# spring_2020_swarm.net
KiCad netlist of a schematic drawn in EAGLE
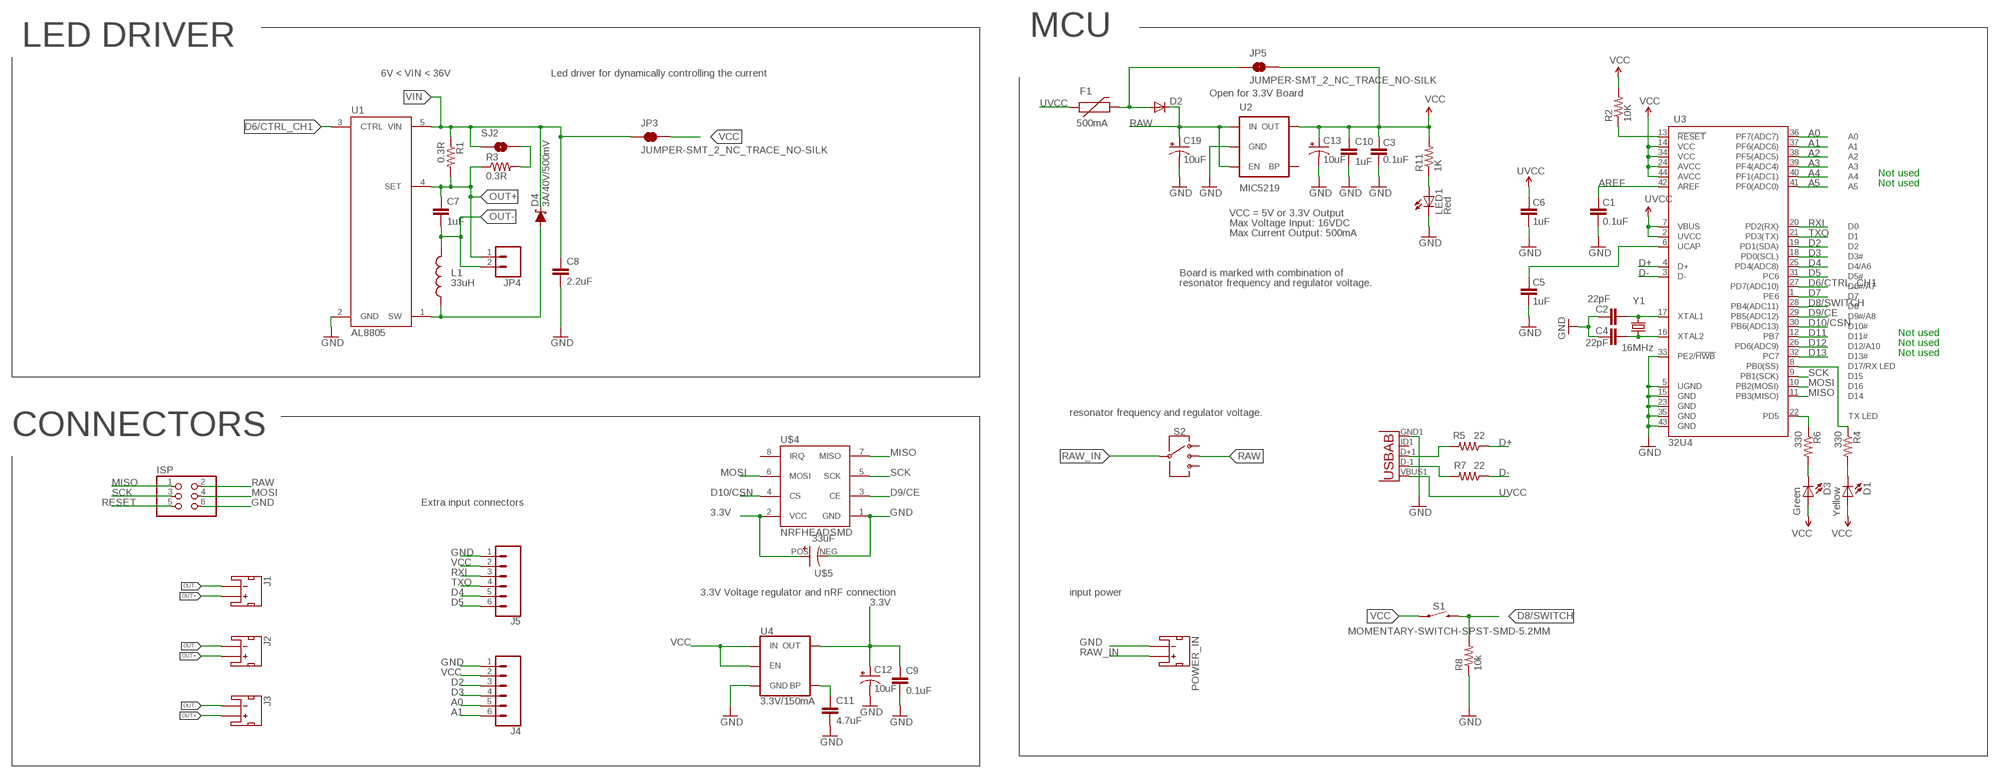
[diagram p0: schematic, sheet 1]

(export (version "E")
  (design (tool "Eeschema 10.0.6"))
  (components
    (comp (ref "C1")
      (value "0.1uF")
      (footprint "eagle-import:0603-CAP")
      (libsource (lib "eagle-import") (part "CAP0603-CAP"))
    )
    (comp (ref "C2")
      (value "22pF")
      (footprint "eagle-import:0603-CAP")
      (libsource (lib "eagle-import") (part "CAP0603-CAP"))
    )
    (comp (ref "C3")
      (value "0.1uF")
      (footprint "eagle-import:0603-CAP")
      (libsource (lib "eagle-import") (part "CAP0603-CAP"))
    )
    (comp (ref "C4")
      (value "22pF")
      (footprint "eagle-import:0603-CAP")
      (libsource (lib "eagle-import") (part "CAP0603-CAP"))
    )
    (comp (ref "C5")
      (value "1uF")
      (footprint "eagle-import:0603-CAP")
      (libsource (lib "eagle-import") (part "CAP0603-CAP"))
    )
    (comp (ref "C6")
      (value "1uF")
      (footprint "eagle-import:0603-CAP")
      (libsource (lib "eagle-import") (part "CAP0603-CAP"))
    )
    (comp (ref "C7")
      (value "1uF")
      (footprint "eagle-import:1206-CAP")
      (libsource (lib "eagle-import") (part "1.0UF50V10%(1206)"))
    )
    (comp (ref "C8")
      (value "2.2uF")
      (footprint "eagle-import:1206-CAP")
      (libsource (lib "eagle-import") (part "2.2UF50V10%(1206)"))
    )
    (comp (ref "C9")
      (value "0.1uF")
      (footprint "eagle-import:0603")
      (libsource (lib "eagle-import") (part "0.1UF-0603-25V-5%"))
    )
    (comp (ref "C10")
      (value "1uF")
      (footprint "eagle-import:0603-CAP")
      (libsource (lib "eagle-import") (part "CAP0603-CAP"))
    )
    (comp (ref "C11")
      (value "4.7uF")
      (footprint "eagle-import:0603")
      (libsource (lib "eagle-import") (part "4.7UF0603"))
    )
    (comp (ref "C12")
      (value "10uF")
      (footprint "eagle-import:EIA3216")
      (libsource (lib "eagle-import") (part "CAP_POL1206"))
    )
    (comp (ref "C13")
      (value "10uF")
      (footprint "eagle-import:EIA3216")
      (libsource (lib "eagle-import") (part "CAP_POL1206"))
    )
    (comp (ref "C19")
      (value "10uF")
      (footprint "eagle-import:EIA3216")
      (libsource (lib "eagle-import") (part "CAP_POL1206"))
    )
    (comp (ref "D1")
      (value "Yellow")
      (footprint "eagle-import:LED-0603")
      (libsource (lib "eagle-import") (part "LED0603"))
    )
    (comp (ref "D2")
      (value "DIODESOD")
      (footprint "eagle-import:SOD-323")
      (libsource (lib "eagle-import") (part "DIODESOD"))
    )
    (comp (ref "D3")
      (value "Green")
      (footprint "eagle-import:LED-0603")
      (libsource (lib "eagle-import") (part "LED0603"))
    )
    (comp (ref "D4")
      (value "3A/40V/500mV")
      (footprint "eagle-import:SMA-DIODE")
      (libsource (lib "eagle-import") (part "DIODE-SCHOTTKY-B340A"))
    )
    (comp (ref "F1")
      (value "500mA")
      (footprint "eagle-import:PTC-1206")
      (libsource (lib "eagle-import") (part "PTCSMD"))
    )
    (comp (ref "ISP")
      (value "PINHD-2X3-SMD")
      (footprint "eagle-import:2X03SMD")
      (libsource (lib "eagle-import") (part "PINHD-2X3-SMD"))
    )
    (comp (ref "J1")
      (value "JST_2MM_MALE")
      (footprint "eagle-import:JST-2-SMD")
      (libsource (lib "eagle-import") (part "JST_2MM_MALE"))
    )
    (comp (ref "J2")
      (value "JST_2MM_MALE")
      (footprint "eagle-import:JST-2-SMD")
      (libsource (lib "eagle-import") (part "JST_2MM_MALE"))
    )
    (comp (ref "J3")
      (value "JST_2MM_MALE")
      (footprint "eagle-import:JST-2-SMD")
      (libsource (lib "eagle-import") (part "JST_2MM_MALE"))
    )
    (comp (ref "J4")
      (value "CONN_06SMD-1MM")
      (footprint "eagle-import:1X06-1MM")
      (libsource (lib "eagle-import") (part "CONN_06SMD-1MM"))
    )
    (comp (ref "J5")
      (value "CONN_06SMD-1MM")
      (footprint "eagle-import:1X06-1MM")
      (libsource (lib "eagle-import") (part "CONN_06SMD-1MM"))
    )
    (comp (ref "JP3")
      (value "JUMPER-SMT_2_NC_TRACE_NO-SILK")
      (footprint "eagle-import:SMT-JUMPER_2_NC_TRACE_NO-SILK")
      (libsource (lib "eagle-import") (part "JUMPER-SMT_2_NC_TRACE_NO-SILK"))
    )
    (comp (ref "JP4")
      (value "CONN_02")
      (footprint "eagle-import:1X02")
      (libsource (lib "eagle-import") (part "CONN_02"))
    )
    (comp (ref "JP5")
      (value "JUMPER-SMT_2_NC_TRACE_NO-SILK")
      (footprint "eagle-import:SMT-JUMPER_2_NC_TRACE_NO-SILK")
      (libsource (lib "eagle-import") (part "JUMPER-SMT_2_NC_TRACE_NO-SILK"))
    )
    (comp (ref "L1")
      (value "33uH")
      (footprint "eagle-import:SRN6045")
      (libsource (lib "eagle-import") (part "INDUCTORBOURNS_SRN6045"))
    )
    (comp (ref "LED1")
      (value "Red")
      (footprint "eagle-import:LED-0603")
      (libsource (lib "eagle-import") (part "LED0603"))
    )
    (comp (ref "POWER_IN")
      (value "JST_2MM_MALE")
      (footprint "eagle-import:JST-2-SMD")
      (libsource (lib "eagle-import") (part "JST_2MM_MALE"))
    )
    (comp (ref "R1")
      (value "0.3R")
      (footprint "eagle-import:0805")
      (libsource (lib "eagle-import") (part "0.3OHM-1/8W-1%(0805)"))
    )
    (comp (ref "R2")
      (value "10K")
      (footprint "eagle-import:0603-RES")
      (libsource (lib "eagle-import") (part "RESISTOR0603-RES"))
    )
    (comp (ref "R3")
      (value "0.3R")
      (footprint "eagle-import:0805")
      (libsource (lib "eagle-import") (part "0.3OHM-1/8W-1%(0805)"))
    )
    (comp (ref "R4")
      (value "330")
      (footprint "eagle-import:0603-RES")
      (libsource (lib "eagle-import") (part "RESISTOR0603-RES"))
    )
    (comp (ref "R5")
      (value "22")
      (footprint "eagle-import:0603-RES")
      (libsource (lib "eagle-import") (part "RESISTOR0603-RES"))
    )
    (comp (ref "R6")
      (value "330")
      (footprint "eagle-import:0603-RES")
      (libsource (lib "eagle-import") (part "RESISTOR0603-RES"))
    )
    (comp (ref "R7")
      (value "22")
      (footprint "eagle-import:0603-RES")
      (libsource (lib "eagle-import") (part "RESISTOR0603-RES"))
    )
    (comp (ref "R8")
      (value "10k")
      (footprint "eagle-import:0603-RES")
      (libsource (lib "eagle-import") (part "RESISTOR0603-RES"))
    )
    (comp (ref "R11")
      (value "1K")
      (footprint "eagle-import:0603-RES")
      (libsource (lib "eagle-import") (part "RESISTOR0603-RES"))
    )
    (comp (ref "S1")
      (value "MOMENTARY-SWITCH-SPST-SMD-5.2MM")
      (footprint "eagle-import:TACTILE_SWITCH_SMD_5.2MM")
      (libsource (lib "eagle-import") (part "MOMENTARY-SWITCH-SPST-SMD-5.2MM"))
    )
    (comp (ref "S2")
      (value "SWITCH-SP3T-SMD")
      (footprint "eagle-import:SWITCH_SP3T_SMD")
      (libsource (lib "eagle-import") (part "SWITCH-SP3T-SMD"))
    )
    (comp (ref "SJ2")
      (value "NO Jumper")
      (footprint "eagle-import:PAD-JUMPER-2-NO_NO_SILK")
      (libsource (lib "eagle-import") (part "JUMPER-PAD-2-NO"))
    )
    (comp (ref "U$4")
      (value "NRFHEADSMD")
      (footprint "eagle-import:2.54MM")
      (libsource (lib "eagle-import") (part "NRFHEADSMD"))
    )
    (comp (ref "U$5")
      (value "33uF")
      (footprint "eagle-import:PANASONIC-CAP-SMD-C")
      (libsource (lib "eagle-import") (part "POLCAP-PANASONIC-SMD-C"))
    )
    (comp (ref "U1")
      (value "AL8805")
      (footprint "eagle-import:SOT23-5")
      (libsource (lib "eagle-import") (part "AL8805"))
    )
    (comp (ref "U2")
      (value "MIC5219")
      (footprint "eagle-import:SOT23-5")
      (libsource (lib "eagle-import") (part "V_REG_LDOSMD"))
    )
    (comp (ref "U3")
      (value "32U4")
      (footprint "eagle-import:TQFP44")
      (libsource (lib "eagle-import") (part "ATMEGA32U4TQFP-44"))
    )
    (comp (ref "U4")
      (value "3.3V/150mA")
      (footprint "eagle-import:SOT23-5")
      (libsource (lib "eagle-import") (part "V_REG_MIC52053.3V"))
    )
    (comp (ref "X1")
      (value "USB-ABIN&OUT")
      (footprint "eagle-import:USB-AB-MICRO-SMD-V03-IN&OUT")
      (libsource (lib "eagle-import") (part "USB-ABIN&OUT"))
    )
    (comp (ref "Y1")
      (value "16MHz")
      (footprint "eagle-import:CRYSTAL-SMD-5X3")
      (libsource (lib "eagle-import") (part "CRYSTAL5X3"))
    )
  )
  (nets
    (net (code "1") (name "/3.3V") (class "Default")
      (node (ref "C12") (pin "A") (pinfunction "+_A") (pintype "passive"))
      (node (ref "C9") (pin "1") (pinfunction "1_1") (pintype "passive"))
      (node (ref "U$4") (pin "2") (pinfunction "VCC_2") (pintype "bidirectional"))
      (node (ref "U$5") (pin "POS") (pinfunction "+_POS") (pintype "bidirectional"))
      (node (ref "U4") (pin "5") (pinfunction "OUT_5") (pintype "passive"))
    )
    (net (code "2") (name "/A0") (class "Default")
      (node (ref "J4") (pin "5") (pinfunction "5_5") (pintype "passive"))
      (node (ref "U3") (pin "36") (pinfunction "PF7(ADC7)_36") (pintype "bidirectional"))
    )
    (net (code "3") (name "/A1") (class "Default")
      (node (ref "J4") (pin "6") (pinfunction "6_6") (pintype "passive"))
      (node (ref "U3") (pin "37") (pinfunction "PF6(ADC6)_37") (pintype "bidirectional"))
    )
    (net (code "4") (name "/A2") (class "Default")
      (node (ref "U3") (pin "38") (pinfunction "PF5(ADC5)_38") (pintype "bidirectional"))
    )
    (net (code "5") (name "/A3") (class "Default")
      (node (ref "U3") (pin "39") (pinfunction "PF4(ADC4)_39") (pintype "bidirectional"))
    )
    (net (code "6") (name "/A4") (class "Default")
      (node (ref "U3") (pin "40") (pinfunction "PF1(ADC1)_40") (pintype "bidirectional"))
    )
    (net (code "7") (name "/A5") (class "Default")
      (node (ref "U3") (pin "41") (pinfunction "PF0(ADC0)_41") (pintype "bidirectional"))
    )
    (net (code "8") (name "/AREF") (class "Default")
      (node (ref "C1") (pin "2") (pinfunction "2_2") (pintype "passive"))
      (node (ref "U3") (pin "42") (pinfunction "AREF_42") (pintype "bidirectional"))
    )
    (net (code "9") (name "/D+") (class "Default")
      (node (ref "R5") (pin "1") (pinfunction "1_1") (pintype "passive"))
      (node (ref "U3") (pin "4") (pinfunction "D+_4") (pintype "bidirectional"))
    )
    (net (code "10") (name "/D-") (class "Default")
      (node (ref "R7") (pin "1") (pinfunction "1_1") (pintype "passive"))
      (node (ref "U3") (pin "3") (pinfunction "D-_3") (pintype "bidirectional"))
    )
    (net (code "11") (name "/D2") (class "Default")
      (node (ref "J4") (pin "3") (pinfunction "3_3") (pintype "passive"))
      (node (ref "U3") (pin "19") (pinfunction "PD1(SDA)_19") (pintype "bidirectional"))
    )
    (net (code "12") (name "/D3") (class "Default")
      (node (ref "J4") (pin "4") (pinfunction "4_4") (pintype "passive"))
      (node (ref "U3") (pin "18") (pinfunction "PD0(SCL)_18") (pintype "bidirectional"))
    )
    (net (code "13") (name "/D4") (class "Default")
      (node (ref "J5") (pin "5") (pinfunction "5_5") (pintype "passive"))
      (node (ref "U3") (pin "25") (pinfunction "PD4(ADC8)_25") (pintype "bidirectional"))
    )
    (net (code "14") (name "/D5") (class "Default")
      (node (ref "J5") (pin "6") (pinfunction "6_6") (pintype "passive"))
      (node (ref "U3") (pin "31") (pinfunction "PC6_31") (pintype "bidirectional"))
    )
    (net (code "15") (name "/D7") (class "Default")
      (node (ref "U3") (pin "1") (pinfunction "PE6_1") (pintype "bidirectional"))
    )
    (net (code "16") (name "/D9{slash}CE") (class "Default")
      (node (ref "U$4") (pin "3") (pinfunction "CE_3") (pintype "bidirectional"))
      (node (ref "U3") (pin "29") (pinfunction "PB5(ADC12)_29") (pintype "bidirectional"))
    )
    (net (code "17") (name "/D10{slash}CSN") (class "Default")
      (node (ref "U$4") (pin "4") (pinfunction "CS_4") (pintype "bidirectional"))
      (node (ref "U3") (pin "30") (pinfunction "PB6(ADC13)_30") (pintype "bidirectional"))
    )
    (net (code "18") (name "/D11") (class "Default")
      (node (ref "U3") (pin "12") (pinfunction "PB7_12") (pintype "bidirectional"))
    )
    (net (code "19") (name "/D12") (class "Default")
      (node (ref "U3") (pin "26") (pinfunction "PD6(ADC9)_26") (pintype "bidirectional"))
    )
    (net (code "20") (name "/D13") (class "Default")
      (node (ref "U3") (pin "32") (pinfunction "PC7_32") (pintype "bidirectional"))
    )
    (net (code "21") (name "/MISO") (class "Default")
      (node (ref "ISP") (pin "1") (pinfunction "1_1") (pintype "passive"))
      (node (ref "U$4") (pin "7") (pinfunction "MISO_7") (pintype "bidirectional"))
      (node (ref "U3") (pin "11") (pinfunction "PB3(MISO)_11") (pintype "bidirectional"))
    )
    (net (code "22") (name "/MOSI") (class "Default")
      (node (ref "ISP") (pin "4") (pinfunction "4_4") (pintype "passive"))
      (node (ref "U$4") (pin "6") (pinfunction "MOSI_6") (pintype "bidirectional"))
      (node (ref "U3") (pin "10") (pinfunction "PB2(MOSI)_10") (pintype "bidirectional"))
    )
    (net (code "23") (name "/RESET") (class "Default")
      (node (ref "ISP") (pin "5") (pinfunction "5_5") (pintype "passive"))
      (node (ref "R2") (pin "1") (pinfunction "1_1") (pintype "passive"))
      (node (ref "U3") (pin "13") (pinfunction "~{RESET}_13") (pintype "bidirectional"))
    )
    (net (code "24") (name "/RXI") (class "Default")
      (node (ref "J5") (pin "3") (pinfunction "3_3") (pintype "passive"))
      (node (ref "U3") (pin "20") (pinfunction "PD2(RX)_20") (pintype "bidirectional"))
    )
    (net (code "25") (name "/SCK") (class "Default")
      (node (ref "ISP") (pin "3") (pinfunction "3_3") (pintype "passive"))
      (node (ref "U$4") (pin "5") (pinfunction "SCK_5") (pintype "bidirectional"))
      (node (ref "U3") (pin "9") (pinfunction "PB1(SCK)_9") (pintype "bidirectional"))
    )
    (net (code "26") (name "/TXO") (class "Default")
      (node (ref "J5") (pin "4") (pinfunction "4_4") (pintype "passive"))
      (node (ref "U3") (pin "21") (pinfunction "PD3(TX)_21") (pintype "bidirectional"))
    )
    (net (code "27") (name "D6{slash}CTRL_CH1") (class "Default")
      (node (ref "U1") (pin "3") (pinfunction "CTRL_3") (pintype "bidirectional"))
      (node (ref "U3") (pin "27") (pinfunction "PD7(ADC10)_27") (pintype "bidirectional"))
    )
    (net (code "28") (name "D8{slash}SWITCH") (class "Default")
      (node (ref "R8") (pin "2") (pinfunction "2_2") (pintype "passive"))
      (node (ref "S1") (pin "3") (pinfunction "2_3") (pintype "passive"))
      (node (ref "U3") (pin "28") (pinfunction "PB4(ADC11)_28") (pintype "bidirectional"))
    )
    (net (code "29") (name "GND") (class "Default")
      (node (ref "C1") (pin "1") (pinfunction "1_1") (pintype "passive"))
      (node (ref "C10") (pin "2") (pinfunction "2_2") (pintype "passive"))
      (node (ref "C11") (pin "2") (pinfunction "2_2") (pintype "passive"))
      (node (ref "C12") (pin "C") (pinfunction "-_C") (pintype "passive"))
      (node (ref "C13") (pin "C") (pinfunction "-_C") (pintype "passive"))
      (node (ref "C19") (pin "C") (pinfunction "-_C") (pintype "passive"))
      (node (ref "C2") (pin "2") (pinfunction "2_2") (pintype "passive"))
      (node (ref "C3") (pin "1") (pinfunction "1_1") (pintype "passive"))
      (node (ref "C4") (pin "2") (pinfunction "2_2") (pintype "passive"))
      (node (ref "C5") (pin "1") (pinfunction "1_1") (pintype "passive"))
      (node (ref "C6") (pin "1") (pinfunction "1_1") (pintype "passive"))
      (node (ref "C8") (pin "2") (pinfunction "2_2") (pintype "passive"))
      (node (ref "C9") (pin "2") (pinfunction "2_2") (pintype "passive"))
      (node (ref "ISP") (pin "6") (pinfunction "6_6") (pintype "passive"))
      (node (ref "J4") (pin "1") (pinfunction "1_1") (pintype "passive"))
      (node (ref "J5") (pin "1") (pinfunction "1_1") (pintype "passive"))
      (node (ref "LED1") (pin "C") (pinfunction "C_C") (pintype "passive"))
      (node (ref "POWER_IN") (pin "1") (pinfunction "-_1") (pintype "bidirectional"))
      (node (ref "R8") (pin "1") (pinfunction "1_1") (pintype "passive"))
      (node (ref "U$4") (pin "1") (pinfunction "GND_1") (pintype "bidirectional"))
      (node (ref "U$5") (pin "NEG") (pinfunction "-_NEG") (pintype "bidirectional"))
      (node (ref "U1") (pin "2") (pinfunction "GND_2") (pintype "bidirectional"))
      (node (ref "U2") (pin "2") (pinfunction "GND_2") (pintype "input"))
      (node (ref "U3") (pin "15") (pinfunction "GND_15") (pintype "bidirectional"))
      (node (ref "U3") (pin "23") (pinfunction "GND_23") (pintype "bidirectional"))
      (node (ref "U3") (pin "33") (pinfunction "PE2/~{HWB}_33") (pintype "bidirectional"))
      (node (ref "U3") (pin "35") (pinfunction "GND_35") (pintype "bidirectional"))
      (node (ref "U3") (pin "43") (pinfunction "GND_43") (pintype "bidirectional"))
      (node (ref "U3") (pin "5") (pinfunction "UGND_5") (pintype "bidirectional"))
      (node (ref "U4") (pin "2") (pinfunction "GND_2") (pintype "input"))
      (node (ref "X1") (pin "GND1") (pinfunction "GND_GND1") (pintype "bidirectional"))
    )
    (net (code "30") (name "Net-(D1-PadC)") (class "Default")
      (node (ref "D1") (pin "C") (pinfunction "C_C") (pintype "passive"))
      (node (ref "R4") (pin "2") (pinfunction "2_2") (pintype "passive"))
    )
    (net (code "31") (name "Net-(D2-A)") (class "Default")
      (node (ref "D2") (pin "2") (pinfunction "A_2") (pintype "passive"))
      (node (ref "F1") (pin "2") (pinfunction "2_2") (pintype "bidirectional"))
      (node (ref "JP5") (pin "1") (pinfunction "1_1") (pintype "passive"))
    )
    (net (code "32") (name "Net-(D3-PadC)") (class "Default")
      (node (ref "D3") (pin "C") (pinfunction "C_C") (pintype "passive"))
      (node (ref "R6") (pin "2") (pinfunction "2_2") (pintype "passive"))
    )
    (net (code "33") (name "Net-(LED1-PadA)") (class "Default")
      (node (ref "LED1") (pin "A") (pinfunction "A_A") (pintype "passive"))
      (node (ref "R11") (pin "1") (pinfunction "1_1") (pintype "passive"))
    )
    (net (code "34") (name "Net-(R3-Pad2)") (class "Default")
      (node (ref "R3") (pin "2") (pinfunction "2_2") (pintype "passive"))
      (node (ref "SJ2") (pin "2") (pinfunction "2_2") (pintype "passive"))
    )
    (net (code "35") (name "Net-(U1-SW)") (class "Default")
      (node (ref "D4") (pin "A") (pinfunction "A_A") (pintype "passive"))
      (node (ref "L1") (pin "1") (pinfunction "1_1") (pintype "passive"))
      (node (ref "U1") (pin "1") (pinfunction "SW_1") (pintype "bidirectional"))
    )
    (net (code "36") (name "Net-(U3-PB0(SS))") (class "Default")
      (node (ref "R4") (pin "1") (pinfunction "1_1") (pintype "passive"))
      (node (ref "U3") (pin "8") (pinfunction "PB0(SS)_8") (pintype "bidirectional"))
    )
    (net (code "37") (name "Net-(U3-PD5)") (class "Default")
      (node (ref "R6") (pin "1") (pinfunction "1_1") (pintype "passive"))
      (node (ref "U3") (pin "22") (pinfunction "PD5_22") (pintype "bidirectional"))
    )
    (net (code "38") (name "Net-(U3-UCAP)") (class "Default")
      (node (ref "C5") (pin "2") (pinfunction "2_2") (pintype "passive"))
      (node (ref "U3") (pin "6") (pinfunction "UCAP_6") (pintype "bidirectional"))
    )
    (net (code "39") (name "Net-(U3-XTAL1)") (class "Default")
      (node (ref "C2") (pin "1") (pinfunction "1_1") (pintype "passive"))
      (node (ref "U3") (pin "17") (pinfunction "XTAL1_17") (pintype "bidirectional"))
      (node (ref "Y1") (pin "3") (pinfunction "2_3") (pintype "passive"))
    )
    (net (code "40") (name "Net-(U3-XTAL2)") (class "Default")
      (node (ref "C4") (pin "1") (pinfunction "1_1") (pintype "passive"))
      (node (ref "U3") (pin "16") (pinfunction "XTAL2_16") (pintype "bidirectional"))
      (node (ref "Y1") (pin "1") (pinfunction "1_1") (pintype "passive"))
    )
    (net (code "41") (name "Net-(U4-BP)") (class "Default")
      (node (ref "C11") (pin "1") (pinfunction "1_1") (pintype "passive"))
      (node (ref "U4") (pin "4") (pinfunction "BP_4") (pintype "input"))
    )
    (net (code "42") (name "Net-(X1-D+)") (class "Default")
      (node (ref "R5") (pin "2") (pinfunction "2_2") (pintype "passive"))
      (node (ref "X1") (pin "D+1") (pinfunction "D+_D+1") (pintype "bidirectional"))
    )
    (net (code "43") (name "Net-(X1-D-)") (class "Default")
      (node (ref "R7") (pin "2") (pinfunction "2_2") (pintype "passive"))
      (node (ref "X1") (pin "D-1") (pinfunction "D-_D-1") (pintype "bidirectional"))
    )
    (net (code "44") (name "OUT+") (class "Default")
      (node (ref "C7") (pin "1") (pinfunction "1_1") (pintype "passive"))
      (node (ref "J1") (pin "2") (pinfunction "+_2") (pintype "bidirectional"))
      (node (ref "J2") (pin "2") (pinfunction "+_2") (pintype "bidirectional"))
      (node (ref "J3") (pin "2") (pinfunction "+_2") (pintype "bidirectional"))
      (node (ref "JP4") (pin "1") (pinfunction "1_1") (pintype "passive"))
      (node (ref "R1") (pin "2") (pinfunction "2_2") (pintype "passive"))
      (node (ref "R3") (pin "1") (pinfunction "1_1") (pintype "passive"))
      (node (ref "U1") (pin "4") (pinfunction "SET_4") (pintype "bidirectional"))
    )
    (net (code "45") (name "OUT-") (class "Default")
      (node (ref "C7") (pin "2") (pinfunction "2_2") (pintype "passive"))
      (node (ref "J1") (pin "1") (pinfunction "-_1") (pintype "bidirectional"))
      (node (ref "J2") (pin "1") (pinfunction "-_1") (pintype "bidirectional"))
      (node (ref "J3") (pin "1") (pinfunction "-_1") (pintype "bidirectional"))
      (node (ref "JP4") (pin "2") (pinfunction "2_2") (pintype "passive"))
      (node (ref "L1") (pin "2") (pinfunction "2_2") (pintype "passive"))
    )
    (net (code "46") (name "RAW") (class "Default")
      (node (ref "C19") (pin "A") (pinfunction "+_A") (pintype "passive"))
      (node (ref "D2") (pin "1") (pinfunction "C_1") (pintype "passive"))
      (node (ref "ISP") (pin "2") (pinfunction "2_2") (pintype "passive"))
      (node (ref "S2") (pin "2") (pinfunction "2_2") (pintype "bidirectional"))
      (node (ref "U2") (pin "1") (pinfunction "IN_1") (pintype "input"))
      (node (ref "U2") (pin "3") (pinfunction "EN_3") (pintype "input"))
    )
    (net (code "47") (name "RAW_IN") (class "Default")
      (node (ref "POWER_IN") (pin "2") (pinfunction "+_2") (pintype "bidirectional"))
      (node (ref "S2") (pin "3") (pinfunction "3_3") (pintype "bidirectional"))
    )
    (net (code "48") (name "UVCC") (class "Default")
      (node (ref "C6") (pin "2") (pinfunction "2_2") (pintype "passive"))
      (node (ref "F1") (pin "1") (pinfunction "1_1") (pintype "bidirectional"))
      (node (ref "U3") (pin "2") (pinfunction "UVCC_2") (pintype "bidirectional"))
      (node (ref "U3") (pin "7") (pinfunction "VBUS_7") (pintype "bidirectional"))
      (node (ref "X1") (pin "VBUS1") (pinfunction "VBUS_VBUS1") (pintype "bidirectional"))
    )
    (net (code "49") (name "VCC") (class "Default")
      (node (ref "C10") (pin "1") (pinfunction "1_1") (pintype "passive"))
      (node (ref "C13") (pin "A") (pinfunction "+_A") (pintype "passive"))
      (node (ref "C3") (pin "2") (pinfunction "2_2") (pintype "passive"))
      (node (ref "D1") (pin "A") (pinfunction "A_A") (pintype "passive"))
      (node (ref "D3") (pin "A") (pinfunction "A_A") (pintype "passive"))
      (node (ref "J4") (pin "2") (pinfunction "2_2") (pintype "passive"))
      (node (ref "J5") (pin "2") (pinfunction "2_2") (pintype "passive"))
      (node (ref "JP3") (pin "2") (pinfunction "2_2") (pintype "passive"))
      (node (ref "JP5") (pin "2") (pinfunction "2_2") (pintype "passive"))
      (node (ref "R11") (pin "2") (pinfunction "2_2") (pintype "passive"))
      (node (ref "R2") (pin "2") (pinfunction "2_2") (pintype "passive"))
      (node (ref "S1") (pin "1") (pinfunction "1_1") (pintype "passive"))
      (node (ref "U2") (pin "5") (pinfunction "OUT_5") (pintype "passive"))
      (node (ref "U3") (pin "14") (pinfunction "VCC_14") (pintype "bidirectional"))
      (node (ref "U3") (pin "24") (pinfunction "AVCC_24") (pintype "bidirectional"))
      (node (ref "U3") (pin "34") (pinfunction "VCC_34") (pintype "bidirectional"))
      (node (ref "U3") (pin "44") (pinfunction "AVCC_44") (pintype "bidirectional"))
      (node (ref "U4") (pin "1") (pinfunction "IN_1") (pintype "input"))
      (node (ref "U4") (pin "3") (pinfunction "EN_3") (pintype "input"))
    )
    (net (code "50") (name "VIN") (class "Default")
      (node (ref "C8") (pin "1") (pinfunction "1_1") (pintype "passive"))
      (node (ref "D4") (pin "C") (pinfunction "C_C") (pintype "passive"))
      (node (ref "JP3") (pin "1") (pinfunction "1_1") (pintype "passive"))
      (node (ref "R1") (pin "1") (pinfunction "1_1") (pintype "passive"))
      (node (ref "SJ2") (pin "1") (pinfunction "1_1") (pintype "passive"))
      (node (ref "U1") (pin "5") (pinfunction "VIN_5") (pintype "bidirectional"))
    )
    (net (code "51") (name "unconnected-(J1-PAD1-PadNC1)") (class "Default")
      (node (ref "J1") (pin "NC1") (pinfunction "PAD1_NC1") (pintype "bidirectional"))
    )
    (net (code "52") (name "unconnected-(J1-PAD2-PadNC2)") (class "Default")
      (node (ref "J1") (pin "NC2") (pinfunction "PAD2_NC2") (pintype "bidirectional"))
    )
    (net (code "53") (name "unconnected-(J2-PAD1-PadNC1)") (class "Default")
      (node (ref "J2") (pin "NC1") (pinfunction "PAD1_NC1") (pintype "bidirectional"))
    )
    (net (code "54") (name "unconnected-(J2-PAD2-PadNC2)") (class "Default")
      (node (ref "J2") (pin "NC2") (pinfunction "PAD2_NC2") (pintype "bidirectional"))
    )
    (net (code "55") (name "unconnected-(J3-PAD1-PadNC1)") (class "Default")
      (node (ref "J3") (pin "NC1") (pinfunction "PAD1_NC1") (pintype "bidirectional"))
    )
    (net (code "56") (name "unconnected-(J3-PAD2-PadNC2)") (class "Default")
      (node (ref "J3") (pin "NC2") (pinfunction "PAD2_NC2") (pintype "bidirectional"))
    )
    (net (code "57") (name "unconnected-(POWER_IN-PAD1-PadNC1)") (class "Default")
      (node (ref "POWER_IN") (pin "NC1") (pinfunction "PAD1_NC1") (pintype "bidirectional"))
    )
    (net (code "58") (name "unconnected-(POWER_IN-PAD2-PadNC2)") (class "Default")
      (node (ref "POWER_IN") (pin "NC2") (pinfunction "PAD2_NC2") (pintype "bidirectional"))
    )
    (net (code "59") (name "unconnected-(S2-Pad1)") (class "Default")
      (node (ref "S2") (pin "1") (pinfunction "1_1") (pintype "bidirectional"))
    )
    (net (code "60") (name "unconnected-(S2-Pad4)") (class "Default")
      (node (ref "S2") (pin "4") (pinfunction "4_4") (pintype "bidirectional"))
    )
    (net (code "61") (name "unconnected-(U$4-IRQ-Pad8)") (class "Default")
      (node (ref "U$4") (pin "8") (pinfunction "IRQ_8") (pintype "bidirectional"))
    )
    (net (code "62") (name "unconnected-(U2-BP-Pad4)") (class "Default")
      (node (ref "U2") (pin "4") (pinfunction "BP_4") (pintype "input"))
    )
    (net (code "63") (name "unconnected-(X1-USBID-PadID1)") (class "Default")
      (node (ref "X1") (pin "ID1") (pinfunction "USBID_ID1") (pintype "bidirectional"))
    )
  )
)
